# Operant-Front-Extended.net
KiCad netlist of a schematic drawn in EAGLE
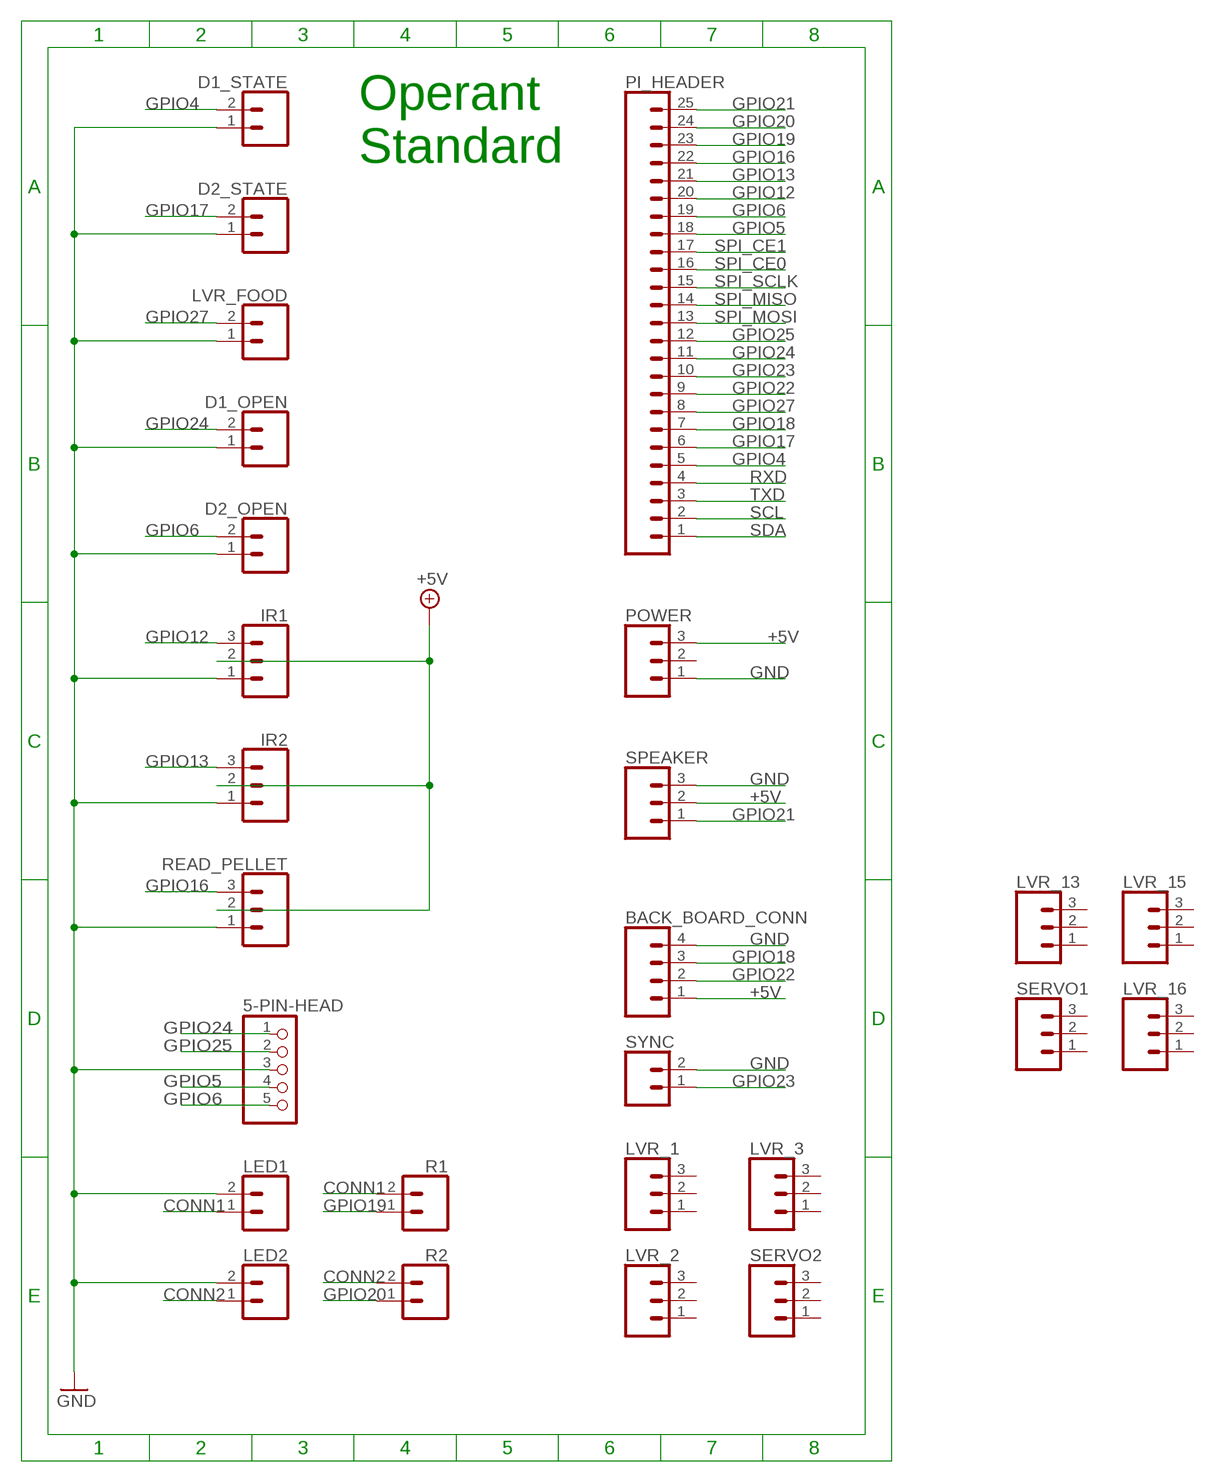
[diagram p0: schematic, sheet 1]

(export (version "E")
  (design (tool "Eeschema 10.0.6"))
  (components
    (comp (ref "5-PIN-HEAD")
      (value "PINHD-1X5")
      (footprint "eagle-import:1X05")
      (libsource (lib "eagle-import") (part "PINHD-1X5"))
    )
    (comp (ref "BACK_BOARD_CONN")
      (value "CONN_04JST-PTH")
      (footprint "eagle-import:JST-4-PTH")
      (libsource (lib "eagle-import") (part "CONN_04JST-PTH"))
    )
    (comp (ref "D1_OPEN")
      (value "CONN_02JST-PTH-2")
      (footprint "eagle-import:JST-2-PTH")
      (libsource (lib "eagle-import") (part "CONN_02JST-PTH-2"))
    )
    (comp (ref "D1_STATE")
      (value "CONN_02JST-PTH-2")
      (footprint "eagle-import:JST-2-PTH")
      (libsource (lib "eagle-import") (part "CONN_02JST-PTH-2"))
    )
    (comp (ref "D2_OPEN")
      (value "CONN_02JST-PTH-2")
      (footprint "eagle-import:JST-2-PTH")
      (libsource (lib "eagle-import") (part "CONN_02JST-PTH-2"))
    )
    (comp (ref "D2_STATE")
      (value "CONN_02JST-PTH-2")
      (footprint "eagle-import:JST-2-PTH")
      (libsource (lib "eagle-import") (part "CONN_02JST-PTH-2"))
    )
    (comp (ref "IR1")
      (value "CONN_03JST-PTH")
      (footprint "eagle-import:JST-3-PTH")
      (libsource (lib "eagle-import") (part "CONN_03JST-PTH"))
    )
    (comp (ref "IR2")
      (value "CONN_03JST-PTH")
      (footprint "eagle-import:JST-3-PTH")
      (libsource (lib "eagle-import") (part "CONN_03JST-PTH"))
    )
    (comp (ref "LED1")
      (value "CONN_02")
      (footprint "eagle-import:1X02")
      (libsource (lib "eagle-import") (part "CONN_02"))
    )
    (comp (ref "LED2")
      (value "CONN_02")
      (footprint "eagle-import:1X02")
      (libsource (lib "eagle-import") (part "CONN_02"))
    )
    (comp (ref "LVR_1")
      (value "CONN_03")
      (footprint "eagle-import:1X03")
      (libsource (lib "eagle-import") (part "CONN_03"))
    )
    (comp (ref "LVR_2")
      (value "CONN_03")
      (footprint "eagle-import:1X03")
      (libsource (lib "eagle-import") (part "CONN_03"))
    )
    (comp (ref "LVR_3")
      (value "CONN_03")
      (footprint "eagle-import:1X03")
      (libsource (lib "eagle-import") (part "CONN_03"))
    )
    (comp (ref "LVR_13")
      (value "CONN_03")
      (footprint "eagle-import:1X03")
      (libsource (lib "eagle-import") (part "CONN_03"))
    )
    (comp (ref "LVR_15")
      (value "CONN_03")
      (footprint "eagle-import:1X03")
      (libsource (lib "eagle-import") (part "CONN_03"))
    )
    (comp (ref "LVR_16")
      (value "CONN_03")
      (footprint "eagle-import:1X03")
      (libsource (lib "eagle-import") (part "CONN_03"))
    )
    (comp (ref "LVR_FOOD")
      (value "CONN_02JST-PTH-2")
      (footprint "eagle-import:JST-2-PTH")
      (libsource (lib "eagle-import") (part "CONN_02JST-PTH-2"))
    )
    (comp (ref "PI_HEADER")
      (value "CONN_25")
      (footprint "eagle-import:1X25")
      (libsource (lib "eagle-import") (part "CONN_25"))
    )
    (comp (ref "POWER")
      (value "CONN_03")
      (footprint "eagle-import:1X03")
      (libsource (lib "eagle-import") (part "CONN_03"))
    )
    (comp (ref "R1")
      (value "CONN_02")
      (footprint "eagle-import:1X02")
      (libsource (lib "eagle-import") (part "CONN_02"))
    )
    (comp (ref "R2")
      (value "CONN_02")
      (footprint "eagle-import:1X02")
      (libsource (lib "eagle-import") (part "CONN_02"))
    )
    (comp (ref "READ_PELLET")
      (value "CONN_03JST-PTH")
      (footprint "eagle-import:JST-3-PTH")
      (libsource (lib "eagle-import") (part "CONN_03JST-PTH"))
    )
    (comp (ref "SERVO1")
      (value "CONN_03")
      (footprint "eagle-import:1X03")
      (libsource (lib "eagle-import") (part "CONN_03"))
    )
    (comp (ref "SERVO2")
      (value "CONN_03")
      (footprint "eagle-import:1X03")
      (libsource (lib "eagle-import") (part "CONN_03"))
    )
    (comp (ref "SPEAKER")
      (value "CONN_03JST-PTH")
      (footprint "eagle-import:JST-3-PTH")
      (libsource (lib "eagle-import") (part "CONN_03JST-PTH"))
    )
    (comp (ref "SYNC")
      (value "CONN_02")
      (footprint "eagle-import:1X02")
      (libsource (lib "eagle-import") (part "CONN_02"))
    )
  )
  (nets
    (net (code "1") (name "+5V") (class "Default")
      (node (ref "BACK_BOARD_CONN") (pin "1") (pinfunction "1_1") (pintype "passive"))
      (node (ref "IR1") (pin "2") (pinfunction "2_2") (pintype "passive"))
      (node (ref "IR2") (pin "2") (pinfunction "2_2") (pintype "passive"))
      (node (ref "POWER") (pin "3") (pinfunction "3_3") (pintype "passive"))
      (node (ref "READ_PELLET") (pin "2") (pinfunction "2_2") (pintype "passive"))
      (node (ref "SPEAKER") (pin "2") (pinfunction "2_2") (pintype "passive"))
    )
    (net (code "2") (name "/CONN1") (class "Default")
      (node (ref "LED1") (pin "1") (pinfunction "1_1") (pintype "passive"))
      (node (ref "R1") (pin "2") (pinfunction "2_2") (pintype "passive"))
    )
    (net (code "3") (name "/CONN2") (class "Default")
      (node (ref "LED2") (pin "1") (pinfunction "1_1") (pintype "passive"))
      (node (ref "R2") (pin "2") (pinfunction "2_2") (pintype "passive"))
    )
    (net (code "4") (name "/GPIO4") (class "Default")
      (node (ref "D1_STATE") (pin "2") (pinfunction "2_2") (pintype "passive"))
      (node (ref "PI_HEADER") (pin "5") (pinfunction "5_5") (pintype "passive"))
    )
    (net (code "5") (name "/GPIO5") (class "Default")
      (node (ref "5-PIN-HEAD") (pin "4") (pinfunction "4_4") (pintype "passive"))
      (node (ref "PI_HEADER") (pin "18") (pinfunction "18_18") (pintype "passive"))
    )
    (net (code "6") (name "/GPIO6") (class "Default")
      (node (ref "5-PIN-HEAD") (pin "5") (pinfunction "5_5") (pintype "passive"))
      (node (ref "D2_OPEN") (pin "2") (pinfunction "2_2") (pintype "passive"))
      (node (ref "PI_HEADER") (pin "19") (pinfunction "19_19") (pintype "passive"))
    )
    (net (code "7") (name "/GPIO12") (class "Default")
      (node (ref "IR1") (pin "3") (pinfunction "3_3") (pintype "passive"))
      (node (ref "PI_HEADER") (pin "20") (pinfunction "20_20") (pintype "passive"))
    )
    (net (code "8") (name "/GPIO13") (class "Default")
      (node (ref "IR2") (pin "3") (pinfunction "3_3") (pintype "passive"))
      (node (ref "PI_HEADER") (pin "21") (pinfunction "21_21") (pintype "passive"))
    )
    (net (code "9") (name "/GPIO16") (class "Default")
      (node (ref "PI_HEADER") (pin "22") (pinfunction "22_22") (pintype "passive"))
      (node (ref "READ_PELLET") (pin "3") (pinfunction "3_3") (pintype "passive"))
    )
    (net (code "10") (name "/GPIO17") (class "Default")
      (node (ref "D2_STATE") (pin "2") (pinfunction "2_2") (pintype "passive"))
      (node (ref "PI_HEADER") (pin "6") (pinfunction "6_6") (pintype "passive"))
    )
    (net (code "11") (name "/GPIO18") (class "Default")
      (node (ref "BACK_BOARD_CONN") (pin "3") (pinfunction "3_3") (pintype "passive"))
      (node (ref "PI_HEADER") (pin "7") (pinfunction "7_7") (pintype "passive"))
    )
    (net (code "12") (name "/GPIO19") (class "Default")
      (node (ref "PI_HEADER") (pin "23") (pinfunction "23_23") (pintype "passive"))
      (node (ref "R1") (pin "1") (pinfunction "1_1") (pintype "passive"))
    )
    (net (code "13") (name "/GPIO20") (class "Default")
      (node (ref "PI_HEADER") (pin "24") (pinfunction "24_24") (pintype "passive"))
      (node (ref "R2") (pin "1") (pinfunction "1_1") (pintype "passive"))
    )
    (net (code "14") (name "/GPIO21") (class "Default")
      (node (ref "PI_HEADER") (pin "25") (pinfunction "25_25") (pintype "passive"))
      (node (ref "SPEAKER") (pin "1") (pinfunction "1_1") (pintype "passive"))
    )
    (net (code "15") (name "/GPIO22") (class "Default")
      (node (ref "BACK_BOARD_CONN") (pin "2") (pinfunction "2_2") (pintype "passive"))
      (node (ref "PI_HEADER") (pin "9") (pinfunction "9_9") (pintype "passive"))
    )
    (net (code "16") (name "/GPIO23") (class "Default")
      (node (ref "PI_HEADER") (pin "10") (pinfunction "10_10") (pintype "passive"))
      (node (ref "SYNC") (pin "1") (pinfunction "1_1") (pintype "passive"))
    )
    (net (code "17") (name "/GPIO24") (class "Default")
      (node (ref "5-PIN-HEAD") (pin "1") (pinfunction "1_1") (pintype "passive"))
      (node (ref "D1_OPEN") (pin "2") (pinfunction "2_2") (pintype "passive"))
      (node (ref "PI_HEADER") (pin "11") (pinfunction "11_11") (pintype "passive"))
    )
    (net (code "18") (name "/GPIO25") (class "Default")
      (node (ref "5-PIN-HEAD") (pin "2") (pinfunction "2_2") (pintype "passive"))
      (node (ref "PI_HEADER") (pin "12") (pinfunction "12_12") (pintype "passive"))
    )
    (net (code "19") (name "/GPIO27") (class "Default")
      (node (ref "LVR_FOOD") (pin "2") (pinfunction "2_2") (pintype "passive"))
      (node (ref "PI_HEADER") (pin "8") (pinfunction "8_8") (pintype "passive"))
    )
    (net (code "20") (name "/RXD") (class "Default")
      (node (ref "PI_HEADER") (pin "4") (pinfunction "4_4") (pintype "passive"))
    )
    (net (code "21") (name "/SCL") (class "Default")
      (node (ref "PI_HEADER") (pin "2") (pinfunction "2_2") (pintype "passive"))
    )
    (net (code "22") (name "/SDA") (class "Default")
      (node (ref "PI_HEADER") (pin "1") (pinfunction "1_1") (pintype "passive"))
    )
    (net (code "23") (name "/SPI_CE0") (class "Default")
      (node (ref "PI_HEADER") (pin "16") (pinfunction "16_16") (pintype "passive"))
    )
    (net (code "24") (name "/SPI_CE1") (class "Default")
      (node (ref "PI_HEADER") (pin "17") (pinfunction "17_17") (pintype "passive"))
    )
    (net (code "25") (name "/SPI_MISO") (class "Default")
      (node (ref "PI_HEADER") (pin "14") (pinfunction "14_14") (pintype "passive"))
    )
    (net (code "26") (name "/SPI_MOSI") (class "Default")
      (node (ref "PI_HEADER") (pin "13") (pinfunction "13_13") (pintype "passive"))
    )
    (net (code "27") (name "/SPI_SCLK") (class "Default")
      (node (ref "PI_HEADER") (pin "15") (pinfunction "15_15") (pintype "passive"))
    )
    (net (code "28") (name "/TXD") (class "Default")
      (node (ref "PI_HEADER") (pin "3") (pinfunction "3_3") (pintype "passive"))
    )
    (net (code "29") (name "GND") (class "Default")
      (node (ref "5-PIN-HEAD") (pin "3") (pinfunction "3_3") (pintype "passive"))
      (node (ref "BACK_BOARD_CONN") (pin "4") (pinfunction "4_4") (pintype "passive"))
      (node (ref "D1_OPEN") (pin "1") (pinfunction "1_1") (pintype "passive"))
      (node (ref "D1_STATE") (pin "1") (pinfunction "1_1") (pintype "passive"))
      (node (ref "D2_OPEN") (pin "1") (pinfunction "1_1") (pintype "passive"))
      (node (ref "D2_STATE") (pin "1") (pinfunction "1_1") (pintype "passive"))
      (node (ref "IR1") (pin "1") (pinfunction "1_1") (pintype "passive"))
      (node (ref "IR2") (pin "1") (pinfunction "1_1") (pintype "passive"))
      (node (ref "LED1") (pin "2") (pinfunction "2_2") (pintype "passive"))
      (node (ref "LED2") (pin "2") (pinfunction "2_2") (pintype "passive"))
      (node (ref "LVR_FOOD") (pin "1") (pinfunction "1_1") (pintype "passive"))
      (node (ref "POWER") (pin "1") (pinfunction "1_1") (pintype "passive"))
      (node (ref "READ_PELLET") (pin "1") (pinfunction "1_1") (pintype "passive"))
      (node (ref "SPEAKER") (pin "3") (pinfunction "3_3") (pintype "passive"))
      (node (ref "SYNC") (pin "2") (pinfunction "2_2") (pintype "passive"))
    )
    (net (code "30") (name "unconnected-(LVR_1-Pad1)") (class "Default")
      (node (ref "LVR_1") (pin "1") (pinfunction "1_1") (pintype "passive"))
    )
    (net (code "31") (name "unconnected-(LVR_1-Pad2)") (class "Default")
      (node (ref "LVR_1") (pin "2") (pinfunction "2_2") (pintype "passive"))
    )
    (net (code "32") (name "unconnected-(LVR_1-Pad3)") (class "Default")
      (node (ref "LVR_1") (pin "3") (pinfunction "3_3") (pintype "passive"))
    )
    (net (code "33") (name "unconnected-(LVR_2-Pad1)") (class "Default")
      (node (ref "LVR_2") (pin "1") (pinfunction "1_1") (pintype "passive"))
    )
    (net (code "34") (name "unconnected-(LVR_2-Pad2)") (class "Default")
      (node (ref "LVR_2") (pin "2") (pinfunction "2_2") (pintype "passive"))
    )
    (net (code "35") (name "unconnected-(LVR_2-Pad3)") (class "Default")
      (node (ref "LVR_2") (pin "3") (pinfunction "3_3") (pintype "passive"))
    )
    (net (code "36") (name "unconnected-(LVR_3-Pad1)") (class "Default")
      (node (ref "LVR_3") (pin "1") (pinfunction "1_1") (pintype "passive"))
    )
    (net (code "37") (name "unconnected-(LVR_3-Pad2)") (class "Default")
      (node (ref "LVR_3") (pin "2") (pinfunction "2_2") (pintype "passive"))
    )
    (net (code "38") (name "unconnected-(LVR_3-Pad3)") (class "Default")
      (node (ref "LVR_3") (pin "3") (pinfunction "3_3") (pintype "passive"))
    )
    (net (code "39") (name "unconnected-(LVR_13-Pad1)") (class "Default")
      (node (ref "LVR_13") (pin "1") (pinfunction "1_1") (pintype "passive"))
    )
    (net (code "40") (name "unconnected-(LVR_13-Pad2)") (class "Default")
      (node (ref "LVR_13") (pin "2") (pinfunction "2_2") (pintype "passive"))
    )
    (net (code "41") (name "unconnected-(LVR_13-Pad3)") (class "Default")
      (node (ref "LVR_13") (pin "3") (pinfunction "3_3") (pintype "passive"))
    )
    (net (code "42") (name "unconnected-(LVR_15-Pad1)") (class "Default")
      (node (ref "LVR_15") (pin "1") (pinfunction "1_1") (pintype "passive"))
    )
    (net (code "43") (name "unconnected-(LVR_15-Pad2)") (class "Default")
      (node (ref "LVR_15") (pin "2") (pinfunction "2_2") (pintype "passive"))
    )
    (net (code "44") (name "unconnected-(LVR_15-Pad3)") (class "Default")
      (node (ref "LVR_15") (pin "3") (pinfunction "3_3") (pintype "passive"))
    )
    (net (code "45") (name "unconnected-(LVR_16-Pad1)") (class "Default")
      (node (ref "LVR_16") (pin "1") (pinfunction "1_1") (pintype "passive"))
    )
    (net (code "46") (name "unconnected-(LVR_16-Pad2)") (class "Default")
      (node (ref "LVR_16") (pin "2") (pinfunction "2_2") (pintype "passive"))
    )
    (net (code "47") (name "unconnected-(LVR_16-Pad3)") (class "Default")
      (node (ref "LVR_16") (pin "3") (pinfunction "3_3") (pintype "passive"))
    )
    (net (code "48") (name "unconnected-(POWER-Pad2)") (class "Default")
      (node (ref "POWER") (pin "2") (pinfunction "2_2") (pintype "passive"))
    )
    (net (code "49") (name "unconnected-(SERVO1-Pad1)") (class "Default")
      (node (ref "SERVO1") (pin "1") (pinfunction "1_1") (pintype "passive"))
    )
    (net (code "50") (name "unconnected-(SERVO1-Pad2)") (class "Default")
      (node (ref "SERVO1") (pin "2") (pinfunction "2_2") (pintype "passive"))
    )
    (net (code "51") (name "unconnected-(SERVO1-Pad3)") (class "Default")
      (node (ref "SERVO1") (pin "3") (pinfunction "3_3") (pintype "passive"))
    )
    (net (code "52") (name "unconnected-(SERVO2-Pad1)") (class "Default")
      (node (ref "SERVO2") (pin "1") (pinfunction "1_1") (pintype "passive"))
    )
    (net (code "53") (name "unconnected-(SERVO2-Pad2)") (class "Default")
      (node (ref "SERVO2") (pin "2") (pinfunction "2_2") (pintype "passive"))
    )
    (net (code "54") (name "unconnected-(SERVO2-Pad3)") (class "Default")
      (node (ref "SERVO2") (pin "3") (pinfunction "3_3") (pintype "passive"))
    )
  )
)
